# ZigBee.net
KiCad netlist of a schematic drawn in Altium Designer
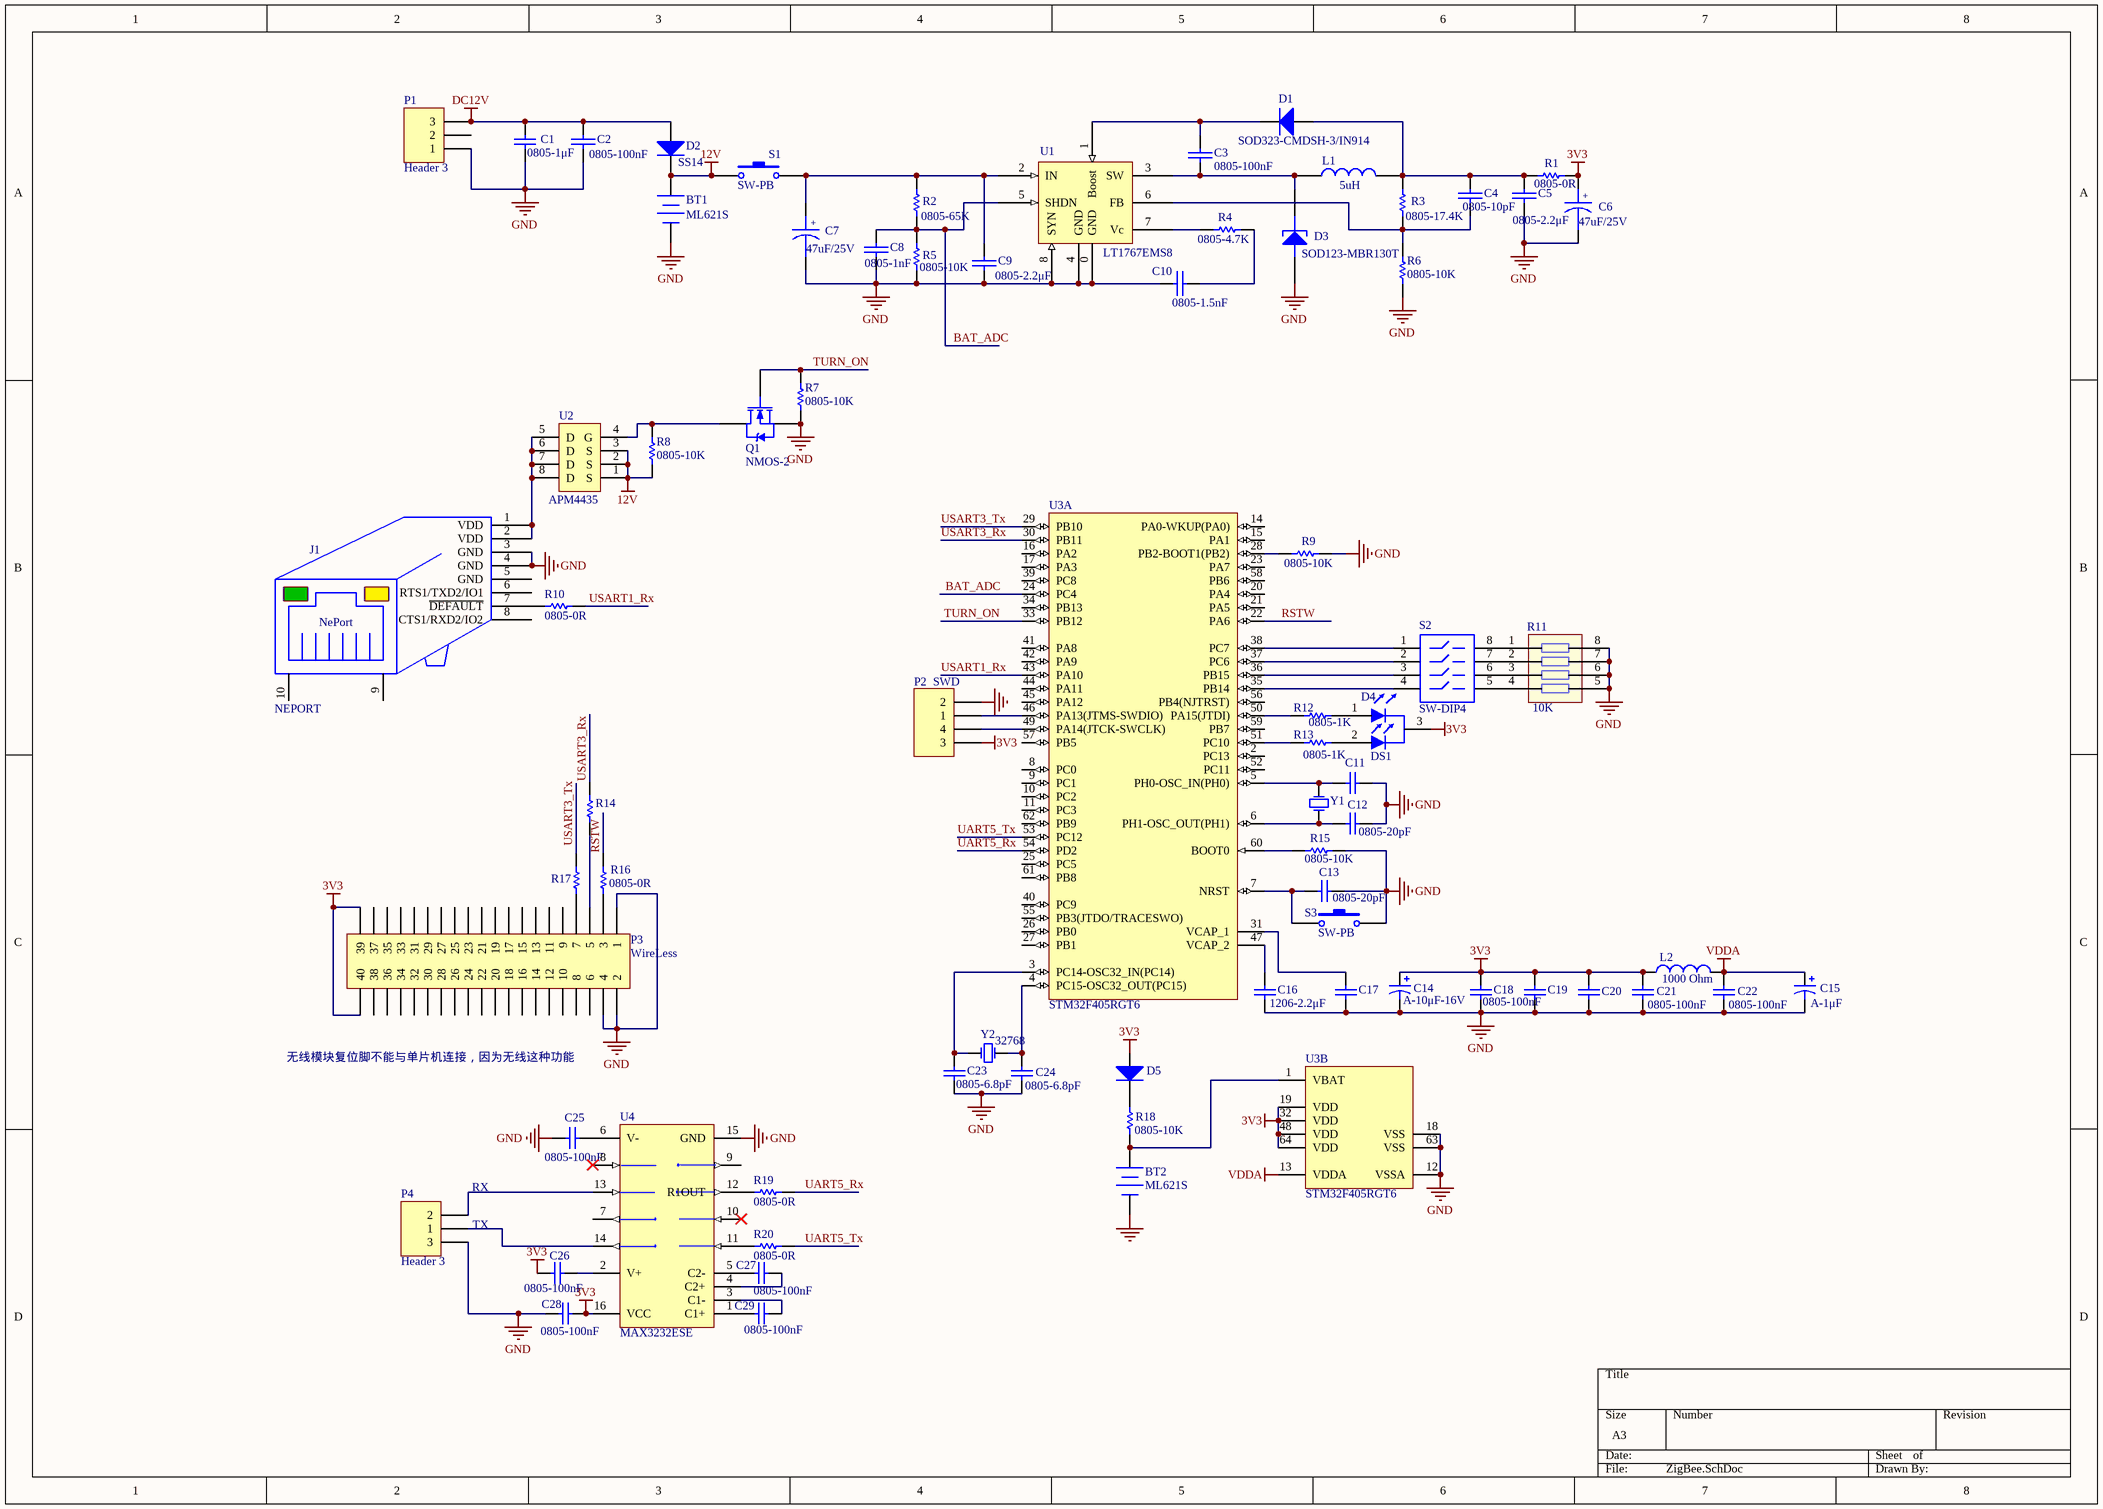
[diagram p0: ZigBee.SchDoc]

(export (version "E")
  (design (tool "Eeschema 10.0.6"))
  (components
    (comp (ref "BT1")
      (value "ML621S")
      (footprint "VH-3.96-2")
      (description "Multicell Battery")
      (fields (field (name "PUBLISHER") "Altium Limited"))
      (libsource (lib "Miscellaneous Devices") (part "Battery"))
    )
    (comp (ref "BT2")
      (value "ML621S")
      (footprint "ML621")
      (description "Multicell Battery")
      (fields (field (name "PUBLISHER") "Altium Limited"))
      (libsource (lib "Miscellaneous Devices") (part "Battery"))
    )
    (comp (ref "C1")
      (value "0805-1μF")
      (footprint "0805C")
      (description "Capacitor")
      (fields (field (name "PUBLISHER") "Altium Limited"))
      (libsource (lib "Miscellaneous Devices") (part "Cap"))
    )
    (comp (ref "C2")
      (value "0805-100nF")
      (footprint "0805C")
      (description "Capacitor")
      (libsource (lib "采集器") (part "普通电容"))
    )
    (comp (ref "C3")
      (value "0805-100nF")
      (footprint "0805C")
      (description "Capacitor")
      (libsource (lib "采集器") (part "普通电容"))
    )
    (comp (ref "C4")
      (value "0805-10pF")
      (footprint "0805C")
      (description "Capacitor")
      (libsource (lib "采集器") (part "普通电容"))
    )
    (comp (ref "C5")
      (value "0805-2.2μF")
      (footprint "0805C")
      (description "Capacitor")
      (libsource (lib "采集器") (part "普通电容"))
    )
    (comp (ref "C6")
      (value "47uF/25V")
      (footprint "SMD-47uF/25V")
      (description "Capacitor")
      (libsource (lib "采集器") (part "电解电容"))
    )
    (comp (ref "C7")
      (value "47uF/25V")
      (footprint "SMD-47uF/25V")
      (description "Capacitor")
      (libsource (lib "采集器") (part "电解电容"))
    )
    (comp (ref "C8")
      (value "0805-1nF")
      (footprint "0805C")
      (description "Capacitor")
      (libsource (lib "采集器") (part "普通电容"))
    )
    (comp (ref "C9")
      (value "0805-2.2μF")
      (footprint "0805C")
      (description "Capacitor")
      (libsource (lib "采集器") (part "普通电容"))
    )
    (comp (ref "C10")
      (value "0805-1.5nF")
      (footprint "0805C")
      (description "Capacitor")
      (libsource (lib "采集器") (part "普通电容"))
    )
    (comp (ref "C11")
      (value "0805-20pF")
      (footprint "0805C")
      (description "Capacitor")
      (fields (field (name "PUBLISHER") "Altium Limited"))
      (libsource (lib "Miscellaneous Devices") (part "Cap"))
    )
    (comp (ref "C12")
      (value "0805-20pF")
      (footprint "0805C")
      (description "Capacitor")
      (fields (field (name "PUBLISHER") "Altium Limited"))
      (libsource (lib "Miscellaneous Devices") (part "Cap"))
    )
    (comp (ref "C13")
      (value "0805-20pF")
      (footprint "0805C")
      (description "Capacitor")
      (fields (field (name "PUBLISHER") "Altium Limited"))
      (libsource (lib "Miscellaneous Devices") (part "Cap"))
    )
    (comp (ref "C14")
      (value "A-10μF-16V")
      (footprint "TANA")
      (description "Polarized Capacitor (Radial)")
      (fields (field (name "PUBLISHER") "Altium Limited"))
      (libsource (lib "Miscellaneous Devices") (part "Cap Pol1"))
    )
    (comp (ref "C15")
      (value "A-1μF")
      (footprint "TANA")
      (description "Polarized Capacitor (Radial)")
      (fields (field (name "PUBLISHER") "Altium Limited"))
      (libsource (lib "Miscellaneous Devices") (part "Cap Pol1"))
    )
    (comp (ref "C16")
      (value "1206-2.2μF")
      (description "Capacitor")
      (fields (field (name "PUBLISHER") "Altium Limited"))
      (libsource (lib "Miscellaneous Devices") (part "Cap"))
    )
    (comp (ref "C17")
      (value "1206-2.2μF")
      (description "Capacitor")
      (fields (field (name "PUBLISHER") "Altium Limited"))
      (libsource (lib "Miscellaneous Devices") (part "Cap"))
    )
    (comp (ref "C18")
      (value "0805-100nF")
      (footprint "0805C")
      (description "Capacitor")
      (fields (field (name "PUBLISHER") "Altium Limited"))
      (libsource (lib "Miscellaneous Devices") (part "Cap"))
    )
    (comp (ref "C19")
      (value "0805-100nF")
      (footprint "0805C")
      (description "Capacitor")
      (fields (field (name "PUBLISHER") "Altium Limited"))
      (libsource (lib "Miscellaneous Devices") (part "Cap"))
    )
    (comp (ref "C20")
      (value "0805-100nF")
      (footprint "0805C")
      (description "Capacitor")
      (fields (field (name "PUBLISHER") "Altium Limited"))
      (libsource (lib "Miscellaneous Devices") (part "Cap"))
    )
    (comp (ref "C21")
      (value "0805-100nF")
      (footprint "0805C")
      (description "Capacitor")
      (fields (field (name "PUBLISHER") "Altium Limited"))
      (libsource (lib "Miscellaneous Devices") (part "Cap"))
    )
    (comp (ref "C22")
      (value "0805-100nF")
      (footprint "0805C")
      (description "Capacitor")
      (fields (field (name "PUBLISHER") "Altium Limited"))
      (libsource (lib "Miscellaneous Devices") (part "Cap"))
    )
    (comp (ref "C23")
      (value "0805-6.8pF")
      (footprint "0805C")
      (description "Capacitor")
      (fields (field (name "PUBLISHER") "Altium Limited"))
      (libsource (lib "Miscellaneous Devices") (part "Cap"))
    )
    (comp (ref "C24")
      (value "0805-6.8pF")
      (footprint "0805C")
      (description "Capacitor")
      (fields (field (name "PUBLISHER") "Altium Limited"))
      (libsource (lib "Miscellaneous Devices") (part "Cap"))
    )
    (comp (ref "C25")
      (value "0805-100nF")
      (footprint "0805C")
      (description "Capacitor")
      (fields (field (name "PUBLISHER") "Altium Limited"))
      (libsource (lib "Miscellaneous Devices") (part "Cap"))
    )
    (comp (ref "C26")
      (value "0805-100nF")
      (footprint "0805C")
      (description "Capacitor")
      (fields (field (name "PUBLISHER") "Altium Limited"))
      (libsource (lib "Miscellaneous Devices") (part "Cap"))
    )
    (comp (ref "C27")
      (value "0805-100nF")
      (footprint "0805C")
      (description "Capacitor")
      (fields (field (name "PUBLISHER") "Altium Limited"))
      (libsource (lib "Miscellaneous Devices") (part "Cap"))
    )
    (comp (ref "C28")
      (value "0805-100nF")
      (footprint "0805C")
      (description "Capacitor")
      (fields (field (name "PUBLISHER") "Altium Limited"))
      (libsource (lib "Miscellaneous Devices") (part "Cap"))
    )
    (comp (ref "C29")
      (value "0805-100nF")
      (footprint "0805C")
      (description "Capacitor")
      (fields (field (name "PUBLISHER") "Altium Limited"))
      (libsource (lib "Miscellaneous Devices") (part "Cap"))
    )
    (comp (ref "D1")
      (value "SOD323-CMDSH-3/IN914")
      (footprint "SOD-323")
      (libsource (lib "采集器") (part "DIODE"))
    )
    (comp (ref "D2") (value "SS14") (footprint "DO-214AC") (libsource (lib "采集器") (part "DIODE")))
    (comp (ref "D3")
      (value "SOD123-MBR130T")
      (footprint "SOD123/X.85")
      (description "Tunnel FDiode")
      (libsource (lib "采集器") (part "TUNNEL"))
    )
    (comp (ref "D4") (value "DS1") (footprint "5MM/F5") (libsource (lib "SCHKU") (part "DS1")))
    (comp (ref "D5")
      (value "1N4148")
      (footprint "SOD-80/MLL34")
      (description "High Conductance Fast Diode")
      (fields (field (name "PUBLISHER") "Altium Limited"))
      (libsource (lib "Miscellaneous Devices") (part "Diode 1N4148"))
    )
    (comp (ref "J1")
      (value "NEPORT")
      (footprint "RJ45_8P8C")
      (description "serial to ethernet RJ45 jack")
      (libsource (lib "Neport") (part "NEPORT"))
    )
    (comp (ref "L1") (value "5uH") (footprint "SMD") (libsource (lib "采集器") (part "INDUCTOR")))
    (comp (ref "L2")
      (value "1000 Ohm")
      (footprint "INDC4516AM")
      (description "BLM41PG102SN1L\\CBW451616U900")
      (fields (field (name "PUBLISHER") "Altium Limited"))
      (libsource (lib "Miscellaneous Devices") (part "Inductor"))
    )
    (comp (ref "P1")
      (value "Header 3")
      (footprint "XH-2.54-3")
      (description "Header, 3-Pin")
      (fields (field (name "PUBLISHER") "Altium Limited"))
      (libsource (lib "Miscellaneous Connectors") (part "Header 3"))
    )
    (comp (ref "P2")
      (value "SWD")
      (footprint "HDR1X4")
      (description "Header, 4-Pin")
      (fields (field (name "PUBLISHER") "Altium Limited"))
      (libsource (lib "Miscellaneous Connectors") (part "Header 4"))
    )
    (comp (ref "P3")
      (value "WireLess")
      (footprint "SMALL/MIDDLE OEM MODEM")
      (description "Header, 20-Pin, Dual row")
      (fields (field (name "PUBLISHER") "Altium Limited"))
      (libsource (lib "Miscellaneous Connectors") (part "Header 20X2"))
    )
    (comp (ref "P4")
      (value "Header 3")
      (footprint "XH-2.54-3")
      (description "Header, 3-Pin")
      (fields (field (name "PUBLISHER") "Altium Limited"))
      (libsource (lib "") (part "Header 3_1"))
    )
    (comp (ref "Q1")
      (value "NMOS-2")
      (footprint "TO-220AB")
      (description "N-Channel Power MOSFET")
      (fields (field (name "PUBLISHER") "Altium Limited"))
      (libsource (lib "Miscellaneous Devices") (part "NMOS-2"))
    )
    (comp (ref "R1")
      (value "0805-0R")
      (footprint "0805")
      (description "Resistor")
      (fields (field (name "PUBLISHER") "Altium Limited"))
      (libsource (lib "Miscellaneous Devices") (part "Res1"))
    )
    (comp (ref "R2")
      (value "0805-65K")
      (footprint "0805")
      (description "Resistor")
      (fields (field (name "PUBLISHER") "Altium Limited"))
      (libsource (lib "Miscellaneous Devices") (part "Res1"))
    )
    (comp (ref "R3")
      (value "0805-17.4K")
      (footprint "0805")
      (description "Resistor")
      (fields (field (name "PUBLISHER") "Altium Limited"))
      (libsource (lib "Miscellaneous Devices") (part "Res1"))
    )
    (comp (ref "R4")
      (value "0805-4.7K")
      (footprint "0805")
      (description "Resistor")
      (fields (field (name "PUBLISHER") "Altium Limited"))
      (libsource (lib "Miscellaneous Devices") (part "Res1"))
    )
    (comp (ref "R5")
      (value "0805-10K")
      (footprint "0805")
      (description "Resistor")
      (fields (field (name "PUBLISHER") "Altium Limited"))
      (libsource (lib "Miscellaneous Devices") (part "Res1"))
    )
    (comp (ref "R6")
      (value "0805-10K")
      (footprint "0805")
      (description "Resistor")
      (fields (field (name "PUBLISHER") "Altium Limited"))
      (libsource (lib "Miscellaneous Devices") (part "Res1"))
    )
    (comp (ref "R7")
      (value "0805-10K")
      (footprint "0805")
      (description "Resistor")
      (fields (field (name "PUBLISHER") "Altium Limited"))
      (libsource (lib "Miscellaneous Devices") (part "Res1"))
    )
    (comp (ref "R8")
      (value "0805-10K")
      (footprint "0805")
      (description "Resistor")
      (fields (field (name "PUBLISHER") "Altium Limited"))
      (libsource (lib "Miscellaneous Devices") (part "Res1"))
    )
    (comp (ref "R9")
      (value "0805-10K")
      (footprint "0805")
      (description "Resistor")
      (fields (field (name "PUBLISHER") "Altium Limited"))
      (libsource (lib "Miscellaneous Devices") (part "Res1"))
    )
    (comp (ref "R10")
      (value "0805-0R")
      (footprint "0805")
      (description "Resistor")
      (fields (field (name "PUBLISHER") "Altium Limited"))
      (libsource (lib "Miscellaneous Devices") (part "Res1"))
    )
    (comp (ref "R11") (value "10K") (footprint "8P4R-0603") (libsource (lib "SCHKU") (part "RN4")))
    (comp (ref "R12")
      (value "0805-1K")
      (footprint "0805")
      (description "Semiconductor Resistor")
      (fields (field (name "PUBLISHER") "Altium Limited"))
      (libsource (lib "Miscellaneous Devices") (part "Res Semi"))
    )
    (comp (ref "R13")
      (value "0805-1K")
      (footprint "0805")
      (description "Semiconductor Resistor")
      (fields (field (name "PUBLISHER") "Altium Limited"))
      (libsource (lib "Miscellaneous Devices") (part "Res Semi"))
    )
    (comp (ref "R14")
      (value "0805-0R")
      (footprint "0805")
      (description "Resistor")
      (fields (field (name "PUBLISHER") "Altium Limited"))
      (libsource (lib "Miscellaneous Devices") (part "Res1"))
    )
    (comp (ref "R15")
      (value "0805-10K")
      (footprint "0805")
      (description "Resistor")
      (fields (field (name "PUBLISHER") "Altium Limited"))
      (libsource (lib "Miscellaneous Devices") (part "Res1"))
    )
    (comp (ref "R16")
      (value "0805-0R")
      (footprint "0805")
      (description "Resistor")
      (fields (field (name "PUBLISHER") "Altium Limited"))
      (libsource (lib "Miscellaneous Devices") (part "Res1"))
    )
    (comp (ref "R17")
      (value "0805-0R")
      (footprint "0805")
      (description "Resistor")
      (fields (field (name "PUBLISHER") "Altium Limited"))
      (libsource (lib "Miscellaneous Devices") (part "Res1"))
    )
    (comp (ref "R18")
      (value "0805-10K")
      (footprint "0805")
      (description "Resistor")
      (fields (field (name "PUBLISHER") "Altium Limited"))
      (libsource (lib "Miscellaneous Devices") (part "Res1"))
    )
    (comp (ref "R19")
      (value "0805-0R")
      (footprint "0805")
      (description "Resistor")
      (fields (field (name "PUBLISHER") "Altium Limited"))
      (libsource (lib "Miscellaneous Devices") (part "Res1"))
    )
    (comp (ref "R20")
      (value "0805-0R")
      (footprint "0805")
      (description "Resistor")
      (fields (field (name "PUBLISHER") "Altium Limited"))
      (libsource (lib "Miscellaneous Devices") (part "Res1"))
    )
    (comp (ref "S1")
      (value "SW-PB")
      (footprint "XH-2.54-2")
      (description "Switch")
      (fields (field (name "PUBLISHER") "Altium Limited"))
      (libsource (lib "Miscellaneous Devices") (part "SW-PB"))
    )
    (comp (ref "S2")
      (value "SW-DIP4")
      (footprint "DIP-8")
      (description "DIP Switch")
      (fields (field (name "PUBLISHER") "Altium Limited"))
      (libsource (lib "Miscellaneous Devices") (part "SW-DIP4"))
    )
    (comp (ref "S3")
      (value "SW-PB")
      (footprint "SW3*4*2MM")
      (description "Switch")
      (fields (field (name "PUBLISHER") "Altium Limited"))
      (libsource (lib "") (part "SW-PB_1"))
    )
    (comp (ref "U1") (value "LT1767EMS8") (footprint "MS8_N") (libsource (lib "采集器") (part "LT1767EMS8")))
    (comp (ref "U2") (value "APM4435") (footprint "SOP-8M") (libsource (lib "BLACKBOX") (part "APM4435")))
    (comp (ref "U3")
      (value "STM32F405RGT6")
      (footprint "TQFP64_M")
      (fields (field (name "MANUFACTURER") "STMicroelectronics"))
      (libsource (lib "STMicroelectronics STM32 F4") (part "STM32F405RGT6"))
    )
    (comp (ref "U4")
      (value "MAX3232ESE")
      (footprint "NSO16_N")
      (description "3.0V TO 5.5V, Low-Power, up to 1Mbps, True RS-232 Transceiver Using Four 0.1µF External Capacitor")
      (fields (field (name "PUBLISHER") "Altium Limited"))
      (libsource (lib "Maxim Communication Transceiver") (part "MAX3232ESE"))
    )
    (comp (ref "Y1")
      (value "8MHz")
      (footprint "XTAL")
      (description "Crystal Oscillator")
      (fields (field (name "PUBLISHER") "Altium Limited"))
      (libsource (lib "Miscellaneous Devices") (part "XTAL"))
    )
    (comp (ref "Y2")
      (value "32768")
      (footprint "1206CY")
      (description "Crystal Oscillator")
      (fields (field (name "PUBLISHER") "Altium Limited"))
      (libsource (lib "Miscellaneous Devices") (part "XTAL"))
    )
  )
  (nets
    (net (code "1") (name "/BAT_ADC") (class "Default")
      (node (ref "C8") (pin "1") (pinfunction "1_1") (pintype "passive"))
      (node (ref "R2") (pin "1") (pinfunction "1_1") (pintype "passive"))
      (node (ref "R5") (pin "2") (pinfunction "2_2") (pintype "passive"))
      (node (ref "U1") (pin "5") (pinfunction "SHDN_5") (pintype "input"))
      (node (ref "U3") (pin "24") (pinfunction "PC4_24") (pintype "bidirectional"))
    )
    (net (code "2") (name "/RSTW") (class "Default")
      (node (ref "R16") (pin "1") (pinfunction "1_1") (pintype "passive"))
      (node (ref "U3") (pin "22") (pinfunction "PA6_22") (pintype "bidirectional"))
    )
    (net (code "3") (name "/TURN_ON") (class "Default")
      (node (ref "Q1") (pin "1") (pinfunction "G_1") (pintype "passive"))
      (node (ref "R7") (pin "2") (pinfunction "2_2") (pintype "passive"))
      (node (ref "U3") (pin "33") (pinfunction "PB12_33") (pintype "bidirectional"))
    )
    (net (code "4") (name "/UART5_Rx") (class "Default")
      (node (ref "R19") (pin "2") (pinfunction "2_2") (pintype "passive"))
      (node (ref "U3") (pin "54") (pinfunction "PD2_54") (pintype "bidirectional"))
    )
    (net (code "5") (name "/UART5_Tx") (class "Default")
      (node (ref "R20") (pin "2") (pinfunction "2_2") (pintype "passive"))
      (node (ref "U3") (pin "53") (pinfunction "PC12_53") (pintype "bidirectional"))
    )
    (net (code "6") (name "/USART1_Rx") (class "Default")
      (node (ref "R10") (pin "1") (pinfunction "1_1") (pintype "passive"))
      (node (ref "U3") (pin "43") (pinfunction "PA10_43") (pintype "bidirectional"))
    )
    (net (code "7") (name "/USART3_Rx") (class "Default")
      (node (ref "R14") (pin "1") (pinfunction "1_1") (pintype "passive"))
      (node (ref "U3") (pin "30") (pinfunction "PB11_30") (pintype "bidirectional"))
    )
    (net (code "8") (name "/USART3_Tx") (class "Default")
      (node (ref "R17") (pin "1") (pinfunction "1_1") (pintype "passive"))
      (node (ref "U3") (pin "29") (pinfunction "PB10_29") (pintype "bidirectional"))
    )
    (net (code "9") (name "3V3") (class "Default")
      (node (ref "C14") (pin "1") (pinfunction "1_1") (pintype "passive"))
      (node (ref "C18") (pin "2") (pinfunction "2_2") (pintype "passive"))
      (node (ref "C19") (pin "2") (pinfunction "2_2") (pintype "passive"))
      (node (ref "C20") (pin "2") (pinfunction "2_2") (pintype "passive"))
      (node (ref "C21") (pin "2") (pinfunction "2_2") (pintype "passive"))
      (node (ref "C26") (pin "2") (pinfunction "2_2") (pintype "passive"))
      (node (ref "C28") (pin "1") (pinfunction "1_1") (pintype "passive"))
      (node (ref "C6") (pin "1") (pinfunction "1_1") (pintype "passive"))
      (node (ref "D4") (pin "3") (pinfunction "3_3") (pintype "passive"))
      (node (ref "D5") (pin "1") (pinfunction "A_1") (pintype "passive"))
      (node (ref "L2") (pin "1") (pinfunction "1_1") (pintype "passive"))
      (node (ref "P2") (pin "3") (pinfunction "3_3") (pintype "passive"))
      (node (ref "P3") (pin "39") (pinfunction "39_39") (pintype "passive"))
      (node (ref "P3") (pin "40") (pinfunction "40_40") (pintype "passive"))
      (node (ref "R1") (pin "2") (pinfunction "2_2") (pintype "passive"))
      (node (ref "U3") (pin "19") (pinfunction "VDD_19") (pintype "power_in"))
      (node (ref "U3") (pin "32") (pinfunction "VDD_32") (pintype "power_in"))
      (node (ref "U3") (pin "48") (pinfunction "VDD_48") (pintype "power_in"))
      (node (ref "U3") (pin "64") (pinfunction "VDD_64") (pintype "power_in"))
      (node (ref "U4") (pin "16") (pinfunction "VCC_16") (pintype "power_in"))
    )
    (net (code "10") (name "12V") (class "Default")
      (node (ref "BT1") (pin "2") (pinfunction "+_2") (pintype "passive"))
      (node (ref "D2") (pin "2") (pinfunction "K_2") (pintype "passive"))
      (node (ref "R8") (pin "1") (pinfunction "1_1") (pintype "passive"))
      (node (ref "S1") (pin "2") (pinfunction "2_2") (pintype "passive"))
      (node (ref "U2") (pin "1") (pinfunction "S_1") (pintype "passive"))
      (node (ref "U2") (pin "2") (pinfunction "S_2") (pintype "passive"))
      (node (ref "U2") (pin "3") (pinfunction "S_3") (pintype "passive"))
    )
    (net (code "11") (name "DC12V") (class "Default")
      (node (ref "C1") (pin "1") (pinfunction "1_1") (pintype "passive"))
      (node (ref "C2") (pin "1") (pinfunction "1_1") (pintype "passive"))
      (node (ref "D2") (pin "1") (pinfunction "A_1") (pintype "passive"))
      (node (ref "P1") (pin "3") (pinfunction "3_3") (pintype "passive"))
    )
    (net (code "12") (name "GND") (class "Default")
      (node (ref "BT1") (pin "1") (pinfunction "-_1") (pintype "passive"))
      (node (ref "BT2") (pin "1") (pinfunction "-_1") (pintype "passive"))
      (node (ref "C1") (pin "2") (pinfunction "2_2") (pintype "passive"))
      (node (ref "C10") (pin "1") (pinfunction "1_1") (pintype "passive"))
      (node (ref "C11") (pin "1") (pinfunction "1_1") (pintype "passive"))
      (node (ref "C12") (pin "1") (pinfunction "1_1") (pintype "passive"))
      (node (ref "C13") (pin "1") (pinfunction "1_1") (pintype "passive"))
      (node (ref "C14") (pin "2") (pinfunction "2_2") (pintype "passive"))
      (node (ref "C15") (pin "2") (pinfunction "2_2") (pintype "passive"))
      (node (ref "C16") (pin "1") (pinfunction "1_1") (pintype "passive"))
      (node (ref "C17") (pin "1") (pinfunction "1_1") (pintype "passive"))
      (node (ref "C18") (pin "1") (pinfunction "1_1") (pintype "passive"))
      (node (ref "C19") (pin "1") (pinfunction "1_1") (pintype "passive"))
      (node (ref "C2") (pin "2") (pinfunction "2_2") (pintype "passive"))
      (node (ref "C20") (pin "1") (pinfunction "1_1") (pintype "passive"))
      (node (ref "C21") (pin "1") (pinfunction "1_1") (pintype "passive"))
      (node (ref "C22") (pin "1") (pinfunction "1_1") (pintype "passive"))
      (node (ref "C23") (pin "2") (pinfunction "2_2") (pintype "passive"))
      (node (ref "C24") (pin "2") (pinfunction "2_2") (pintype "passive"))
      (node (ref "C25") (pin "2") (pinfunction "2_2") (pintype "passive"))
      (node (ref "C28") (pin "2") (pinfunction "2_2") (pintype "passive"))
      (node (ref "C5") (pin "2") (pinfunction "2_2") (pintype "passive"))
      (node (ref "C6") (pin "2") (pinfunction "2_2") (pintype "passive"))
      (node (ref "C7") (pin "2") (pinfunction "2_2") (pintype "passive"))
      (node (ref "C8") (pin "2") (pinfunction "2_2") (pintype "passive"))
      (node (ref "C9") (pin "2") (pinfunction "2_2") (pintype "passive"))
      (node (ref "D3") (pin "1") (pinfunction "A_1") (pintype "passive"))
      (node (ref "J1") (pin "3") (pinfunction "GND_3") (pintype "passive"))
      (node (ref "J1") (pin "4") (pinfunction "GND_4") (pintype "passive"))
      (node (ref "P1") (pin "1") (pinfunction "1_1") (pintype "passive"))
      (node (ref "P2") (pin "2") (pinfunction "2_2") (pintype "passive"))
      (node (ref "P3") (pin "1") (pinfunction "1_1") (pintype "passive"))
      (node (ref "P3") (pin "2") (pinfunction "2_2") (pintype "passive"))
      (node (ref "P3") (pin "4") (pinfunction "4_4") (pintype "passive"))
      (node (ref "P4") (pin "3") (pinfunction "3_3") (pintype "passive"))
      (node (ref "Q1") (pin "3") (pinfunction "D_3") (pintype "passive"))
      (node (ref "R11") (pin "5") (pinfunction "5_5") (pintype "passive"))
      (node (ref "R11") (pin "6") (pinfunction "6_6") (pintype "passive"))
      (node (ref "R11") (pin "7") (pinfunction "7_7") (pintype "passive"))
      (node (ref "R11") (pin "8") (pinfunction "8_8") (pintype "passive"))
      (node (ref "R15") (pin "2") (pinfunction "2_2") (pintype "passive"))
      (node (ref "R5") (pin "1") (pinfunction "1_1") (pintype "passive"))
      (node (ref "R6") (pin "1") (pinfunction "1_1") (pintype "passive"))
      (node (ref "R7") (pin "1") (pinfunction "1_1") (pintype "passive"))
      (node (ref "R9") (pin "2") (pinfunction "2_2") (pintype "passive"))
      (node (ref "S3") (pin "2") (pinfunction "2_2") (pintype "passive"))
      (node (ref "U1") (pin "0") (pinfunction "GND_0") (pintype "passive"))
      (node (ref "U1") (pin "4") (pinfunction "GND_4") (pintype "passive"))
      (node (ref "U1") (pin "8") (pinfunction "SYN_8") (pintype "input"))
      (node (ref "U3") (pin "12") (pinfunction "VSSA_12") (pintype "power_in"))
      (node (ref "U3") (pin "18") (pinfunction "VSS_18") (pintype "power_in"))
      (node (ref "U3") (pin "63") (pinfunction "VSS_63") (pintype "power_in"))
      (node (ref "U4") (pin "15") (pinfunction "GND_15") (pintype "power_in"))
    )
    (net (code "13") (name "Net-(BT2-+)") (class "Default")
      (node (ref "BT2") (pin "2") (pinfunction "+_2") (pintype "passive"))
      (node (ref "R18") (pin "2") (pinfunction "2_2") (pintype "passive"))
      (node (ref "U3") (pin "1") (pinfunction "VBAT_1") (pintype "power_in"))
    )
    (net (code "14") (name "Net-(C10-Pad2)") (class "Default")
      (node (ref "C10") (pin "2") (pinfunction "2_2") (pintype "passive"))
      (node (ref "R4") (pin "1") (pinfunction "1_1") (pintype "passive"))
    )
    (net (code "15") (name "Net-(D1-A)") (class "Default")
      (node (ref "C4") (pin "1") (pinfunction "1_1") (pintype "passive"))
      (node (ref "C5") (pin "1") (pinfunction "1_1") (pintype "passive"))
      (node (ref "D1") (pin "1") (pinfunction "A_1") (pintype "passive"))
      (node (ref "L1") (pin "2") (pinfunction "2_2") (pintype "passive"))
      (node (ref "R1") (pin "1") (pinfunction "1_1") (pintype "passive"))
      (node (ref "R3") (pin "2") (pinfunction "2_2") (pintype "passive"))
    )
    (net (code "16") (name "Net-(D1-K)") (class "Default")
      (node (ref "C3") (pin "1") (pinfunction "1_1") (pintype "passive"))
      (node (ref "D1") (pin "2") (pinfunction "K_2") (pintype "passive"))
      (node (ref "U1") (pin "1") (pinfunction "Boost_1") (pintype "input"))
    )
    (net (code "17") (name "Net-(D3-K)") (class "Default")
      (node (ref "C3") (pin "2") (pinfunction "2_2") (pintype "passive"))
      (node (ref "D3") (pin "2") (pinfunction "K_2") (pintype "passive"))
      (node (ref "L1") (pin "1") (pinfunction "1_1") (pintype "passive"))
      (node (ref "U1") (pin "3") (pinfunction "SW_3") (pintype "passive"))
    )
    (net (code "18") (name "Net-(D4-Pad1)") (class "Default")
      (node (ref "D4") (pin "1") (pinfunction "1_1") (pintype "passive"))
      (node (ref "R12") (pin "2") (pinfunction "2_2") (pintype "passive"))
    )
    (net (code "19") (name "Net-(D4-Pad2)") (class "Default")
      (node (ref "D4") (pin "2") (pinfunction "2_2") (pintype "passive"))
      (node (ref "R13") (pin "2") (pinfunction "2_2") (pintype "passive"))
    )
    (net (code "20") (name "Net-(D5-K)") (class "Default")
      (node (ref "D5") (pin "2") (pinfunction "K_2") (pintype "passive"))
      (node (ref "R18") (pin "1") (pinfunction "1_1") (pintype "passive"))
    )
    (net (code "21") (name "Net-(J1-VDD-Pad1)") (class "Default")
      (node (ref "J1") (pin "1") (pinfunction "VDD_1") (pintype "passive"))
      (node (ref "J1") (pin "2") (pinfunction "VDD_2") (pintype "passive"))
      (node (ref "U2") (pin "5") (pinfunction "D_5") (pintype "passive"))
      (node (ref "U2") (pin "6") (pinfunction "D_6") (pintype "passive"))
      (node (ref "U2") (pin "7") (pinfunction "D_7") (pintype "passive"))
      (node (ref "U2") (pin "8") (pinfunction "D_8") (pintype "passive"))
    )
    (net (code "22") (name "Net-(J1-~{DEFAULT})") (class "Default")
      (node (ref "J1") (pin "7") (pinfunction "~{DEFAULT}_7") (pintype "passive"))
      (node (ref "R10") (pin "2") (pinfunction "2_2") (pintype "passive"))
    )
    (net (code "23") (name "Net-(P3-Pad3)") (class "Default")
      (node (ref "P3") (pin "3") (pinfunction "3_3") (pintype "passive"))
      (node (ref "R16") (pin "2") (pinfunction "2_2") (pintype "passive"))
    )
    (net (code "24") (name "Net-(P3-Pad5)") (class "Default")
      (node (ref "P3") (pin "5") (pinfunction "5_5") (pintype "passive"))
      (node (ref "R14") (pin "2") (pinfunction "2_2") (pintype "passive"))
    )
    (net (code "25") (name "Net-(P3-Pad7)") (class "Default")
      (node (ref "P3") (pin "7") (pinfunction "7_7") (pintype "passive"))
      (node (ref "R17") (pin "2") (pinfunction "2_2") (pintype "passive"))
    )
    (net (code "26") (name "Net-(Q1-S)") (class "Default")
      (node (ref "Q1") (pin "2") (pinfunction "S_2") (pintype "passive"))
      (node (ref "R8") (pin "2") (pinfunction "2_2") (pintype "passive"))
      (node (ref "U2") (pin "4") (pinfunction "G_4") (pintype "passive"))
    )
    (net (code "27") (name "Net-(R11-Pad1)") (class "Default")
      (node (ref "R11") (pin "1") (pinfunction "1_1") (pintype "passive"))
      (node (ref "S2") (pin "8") (pinfunction "8_8") (pintype "passive"))
    )
    (net (code "28") (name "Net-(R11-Pad2)") (class "Default")
      (node (ref "R11") (pin "2") (pinfunction "2_2") (pintype "passive"))
      (node (ref "S2") (pin "7") (pinfunction "7_7") (pintype "passive"))
    )
    (net (code "29") (name "Net-(R11-Pad3)") (class "Default")
      (node (ref "R11") (pin "3") (pinfunction "3_3") (pintype "passive"))
      (node (ref "S2") (pin "6") (pinfunction "6_6") (pintype "passive"))
    )
    (net (code "30") (name "Net-(R11-Pad4)") (class "Default")
      (node (ref "R11") (pin "4") (pinfunction "4_4") (pintype "passive"))
      (node (ref "S2") (pin "5") (pinfunction "5_5") (pintype "passive"))
    )
    (net (code "31") (name "Net-(U1-FB)") (class "Default")
      (node (ref "C4") (pin "2") (pinfunction "2_2") (pintype "passive"))
      (node (ref "R3") (pin "1") (pinfunction "1_1") (pintype "passive"))
      (node (ref "R6") (pin "2") (pinfunction "2_2") (pintype "passive"))
      (node (ref "U1") (pin "6") (pinfunction "FB_6") (pintype "passive"))
    )
    (net (code "32") (name "Net-(U1-IN)") (class "Default")
      (node (ref "C7") (pin "1") (pinfunction "1_1") (pintype "passive"))
      (node (ref "C9") (pin "1") (pinfunction "1_1") (pintype "passive"))
      (node (ref "R2") (pin "2") (pinfunction "2_2") (pintype "passive"))
      (node (ref "S1") (pin "1") (pinfunction "1_1") (pintype "passive"))
      (node (ref "U1") (pin "2") (pinfunction "IN_2") (pintype "input"))
    )
    (net (code "33") (name "Net-(U1-Vc)") (class "Default")
      (node (ref "R4") (pin "2") (pinfunction "2_2") (pintype "passive"))
      (node (ref "U1") (pin "7") (pinfunction "Vc_7") (pintype "passive"))
    )
    (net (code "34") (name "Net-(U3A-BOOT0)") (class "Default")
      (node (ref "R15") (pin "1") (pinfunction "1_1") (pintype "passive"))
      (node (ref "U3") (pin "60") (pinfunction "BOOT0_60") (pintype "input"))
    )
    (net (code "35") (name "Net-(U3A-NRST)") (class "Default")
      (node (ref "C13") (pin "2") (pinfunction "2_2") (pintype "passive"))
      (node (ref "S3") (pin "1") (pinfunction "1_1") (pintype "passive"))
      (node (ref "U3") (pin "7") (pinfunction "NRST_7") (pintype "bidirectional"))
    )
    (net (code "36") (name "Net-(U3A-PA13(JTMS-SWDIO))") (class "Default")
      (node (ref "P2") (pin "1") (pinfunction "1_1") (pintype "passive"))
      (node (ref "U3") (pin "46") (pinfunction "PA13(JTMS-SWDIO)_46") (pintype "bidirectional"))
    )
    (net (code "37") (name "Net-(U3A-PA14(JTCK-SWCLK))") (class "Default")
      (node (ref "P2") (pin "4") (pinfunction "4_4") (pintype "passive"))
      (node (ref "U3") (pin "49") (pinfunction "PA14(JTCK-SWCLK)_49") (pintype "bidirectional"))
    )
    (net (code "38") (name "Net-(U3A-PA15(JTDI))") (class "Default")
      (node (ref "R12") (pin "1") (pinfunction "1_1") (pintype "passive"))
      (node (ref "U3") (pin "50") (pinfunction "PA15(JTDI)_50") (pintype "bidirectional"))
    )
    (net (code "39") (name "Net-(U3A-PB2-BOOT1(PB2))") (class "Default")
      (node (ref "R9") (pin "1") (pinfunction "1_1") (pintype "passive"))
      (node (ref "U3") (pin "28") (pinfunction "PB2-BOOT1(PB2)_28") (pintype "bidirectional"))
    )
    (net (code "40") (name "Net-(U3A-PB14)") (class "Default")
      (node (ref "S2") (pin "4") (pinfunction "4_4") (pintype "passive"))
      (node (ref "U3") (pin "35") (pinfunction "PB14_35") (pintype "bidirectional"))
    )
    (net (code "41") (name "Net-(U3A-PB15)") (class "Default")
      (node (ref "S2") (pin "3") (pinfunction "3_3") (pintype "passive"))
      (node (ref "U3") (pin "36") (pinfunction "PB15_36") (pintype "bidirectional"))
    )
    (net (code "42") (name "Net-(U3A-PC6)") (class "Default")
      (node (ref "S2") (pin "2") (pinfunction "2_2") (pintype "passive"))
      (node (ref "U3") (pin "37") (pinfunction "PC6_37") (pintype "bidirectional"))
    )
    (net (code "43") (name "Net-(U3A-PC7)") (class "Default")
      (node (ref "S2") (pin "1") (pinfunction "1_1") (pintype "passive"))
      (node (ref "U3") (pin "38") (pinfunction "PC7_38") (pintype "bidirectional"))
    )
    (net (code "44") (name "Net-(U3A-PC10)") (class "Default")
      (node (ref "R13") (pin "1") (pinfunction "1_1") (pintype "passive"))
      (node (ref "U3") (pin "51") (pinfunction "PC10_51") (pintype "bidirectional"))
    )
    (net (code "45") (name "Net-(U3A-PC14-OSC32_IN(PC14))") (class "Default")
      (node (ref "C23") (pin "1") (pinfunction "1_1") (pintype "passive"))
      (node (ref "U3") (pin "3") (pinfunction "PC14-OSC32_IN(PC14)_3") (pintype "bidirectional"))
      (node (ref "Y2") (pin "2") (pinfunction "OSC2_2") (pintype "passive"))
    )
    (net (code "46") (name "Net-(U3A-PC15-OSC32_OUT(PC15))") (class "Default")
      (node (ref "C24") (pin "1") (pinfunction "1_1") (pintype "passive"))
      (node (ref "U3") (pin "4") (pinfunction "PC15-OSC32_OUT(PC15)_4") (pintype "bidirectional"))
      (node (ref "Y2") (pin "1") (pinfunction "OSC1_1") (pintype "passive"))
    )
    (net (code "47") (name "Net-(U3A-PH0-OSC_IN(PH0))") (class "Default")
      (node (ref "C11") (pin "2") (pinfunction "2_2") (pintype "passive"))
      (node (ref "U3") (pin "5") (pinfunction "PH0-OSC_IN(PH0)_5") (pintype "bidirectional"))
      (node (ref "Y1") (pin "2") (pinfunction "OSC2_2") (pintype "passive"))
    )
    (net (code "48") (name "Net-(U3A-PH1-OSC_OUT(PH1))") (class "Default")
      (node (ref "C12") (pin "2") (pinfunction "2_2") (pintype "passive"))
      (node (ref "U3") (pin "6") (pinfunction "PH1-OSC_OUT(PH1)_6") (pintype "bidirectional"))
      (node (ref "Y1") (pin "1") (pinfunction "OSC1_1") (pintype "passive"))
    )
    (net (code "49") (name "Net-(U3A-VCAP_1)") (class "Default")
      (node (ref "C17") (pin "2") (pinfunction "2_2") (pintype "passive"))
      (node (ref "U3") (pin "31") (pinfunction "VCAP_1_31") (pintype "power_in"))
    )
    (net (code "50") (name "Net-(U3A-VCAP_2)") (class "Default")
      (node (ref "C16") (pin "2") (pinfunction "2_2") (pintype "passive"))
      (node (ref "U3") (pin "47") (pinfunction "VCAP_2_47") (pintype "power_in"))
    )
    (net (code "51") (name "Net-(U4-C1+)") (class "Default")
      (node (ref "C29") (pin "2") (pinfunction "2_2") (pintype "passive"))
      (node (ref "U4") (pin "1") (pinfunction "C1+_1") (pintype "passive"))
    )
    (net (code "52") (name "Net-(U4-C1-)") (class "Default")
      (node (ref "C29") (pin "1") (pinfunction "1_1") (pintype "passive"))
      (node (ref "U4") (pin "3") (pinfunction "C1-_3") (pintype "passive"))
    )
    (net (code "53") (name "Net-(U4-C2+)") (class "Default")
      (node (ref "C27") (pin "1") (pinfunction "1_1") (pintype "passive"))
      (node (ref "U4") (pin "4") (pinfunction "C2+_4") (pintype "passive"))
    )
    (net (code "54") (name "Net-(U4-C2-)") (class "Default")
      (node (ref "C27") (pin "2") (pinfunction "2_2") (pintype "passive"))
      (node (ref "U4") (pin "5") (pinfunction "C2-_5") (pintype "passive"))
    )
    (net (code "55") (name "Net-(U4-R1IN)") (class "Default")
      (node (ref "P4") (pin "2") (pinfunction "2_2") (pintype "passive"))
      (node (ref "U4") (pin "13") (pinfunction "R1IN_13") (pintype "input"))
    )
    (net (code "56") (name "Net-(U4-R1OUT)") (class "Default")
      (node (ref "R19") (pin "1") (pinfunction "1_1") (pintype "passive"))
      (node (ref "U4") (pin "12") (pinfunction "R1OUT_12") (pintype "output"))
    )
    (net (code "57") (name "Net-(U4-T1IN)") (class "Default")
      (node (ref "R20") (pin "1") (pinfunction "1_1") (pintype "passive"))
      (node (ref "U4") (pin "11") (pinfunction "T1IN_11") (pintype "input"))
    )
    (net (code "58") (name "Net-(U4-T1OUT)") (class "Default")
      (node (ref "P4") (pin "1") (pinfunction "1_1") (pintype "passive"))
      (node (ref "U4") (pin "14") (pinfunction "T1OUT_14") (pintype "output"))
    )
    (net (code "59") (name "Net-(U4-V+)") (class "Default")
      (node (ref "C26") (pin "1") (pinfunction "1_1") (pintype "passive"))
      (node (ref "U4") (pin "2") (pinfunction "V+_2") (pintype "power_in"))
    )
    (net (code "60") (name "Net-(U4-V-)") (class "Default")
      (node (ref "C25") (pin "1") (pinfunction "1_1") (pintype "passive"))
      (node (ref "U4") (pin "6") (pinfunction "V-_6") (pintype "power_in"))
    )
    (net (code "61") (name "VDDA") (class "Default")
      (node (ref "C15") (pin "1") (pinfunction "1_1") (pintype "passive"))
      (node (ref "C22") (pin "2") (pinfunction "2_2") (pintype "passive"))
      (node (ref "L2") (pin "2") (pinfunction "2_2") (pintype "passive"))
      (node (ref "U3") (pin "13") (pinfunction "VDDA_13") (pintype "power_in"))
    )
    (net (code "62") (name "unconnected-(J1-CTS1{slash}RXD2{slash}IO2-Pad8)") (class "Default")
      (node (ref "J1") (pin "8") (pinfunction "CTS1/RXD2/IO2_8") (pintype "passive"))
    )
    (net (code "63") (name "unconnected-(J1-GND-Pad5)") (class "Default")
      (node (ref "J1") (pin "5") (pinfunction "GND_5") (pintype "passive"))
    )
    (net (code "64") (name "unconnected-(J1-RTS1{slash}TXD2{slash}IO1-Pad6)") (class "Default")
      (node (ref "J1") (pin "6") (pinfunction "RTS1/TXD2/IO1_6") (pintype "passive"))
    )
    (net (code "65") (name "unconnected-(J1-SHELL-Pad9)") (class "Default")
      (node (ref "J1") (pin "9") (pinfunction "SHELL_9") (pintype "passive"))
    )
    (net (code "66") (name "unconnected-(J1-SHELL-Pad10)") (class "Default")
      (node (ref "J1") (pin "10") (pinfunction "SHELL_10") (pintype "passive"))
    )
    (net (code "67") (name "unconnected-(P1-Pad2)") (class "Default")
      (node (ref "P1") (pin "2") (pinfunction "2_2") (pintype "passive"))
    )
    (net (code "68") (name "unconnected-(P3-Pad6)") (class "Default")
      (node (ref "P3") (pin "6") (pinfunction "6_6") (pintype "passive"))
    )
    (net (code "69") (name "unconnected-(P3-Pad8)") (class "Default")
      (node (ref "P3") (pin "8") (pinfunction "8_8") (pintype "passive"))
    )
    (net (code "70") (name "unconnected-(P3-Pad9)") (class "Default")
      (node (ref "P3") (pin "9") (pinfunction "9_9") (pintype "passive"))
    )
    (net (code "71") (name "unconnected-(P3-Pad10)") (class "Default")
      (node (ref "P3") (pin "10") (pinfunction "10_10") (pintype "passive"))
    )
    (net (code "72") (name "unconnected-(P3-Pad11)") (class "Default")
      (node (ref "P3") (pin "11") (pinfunction "11_11") (pintype "passive"))
    )
    (net (code "73") (name "unconnected-(P3-Pad12)") (class "Default")
      (node (ref "P3") (pin "12") (pinfunction "12_12") (pintype "passive"))
    )
    (net (code "74") (name "unconnected-(P3-Pad13)") (class "Default")
      (node (ref "P3") (pin "13") (pinfunction "13_13") (pintype "passive"))
    )
    (net (code "75") (name "unconnected-(P3-Pad14)") (class "Default")
      (node (ref "P3") (pin "14") (pinfunction "14_14") (pintype "passive"))
    )
    (net (code "76") (name "unconnected-(P3-Pad15)") (class "Default")
      (node (ref "P3") (pin "15") (pinfunction "15_15") (pintype "passive"))
    )
    (net (code "77") (name "unconnected-(P3-Pad16)") (class "Default")
      (node (ref "P3") (pin "16") (pinfunction "16_16") (pintype "passive"))
    )
    (net (code "78") (name "unconnected-(P3-Pad17)") (class "Default")
      (node (ref "P3") (pin "17") (pinfunction "17_17") (pintype "passive"))
    )
    (net (code "79") (name "unconnected-(P3-Pad18)") (class "Default")
      (node (ref "P3") (pin "18") (pinfunction "18_18") (pintype "passive"))
    )
    (net (code "80") (name "unconnected-(P3-Pad19)") (class "Default")
      (node (ref "P3") (pin "19") (pinfunction "19_19") (pintype "passive"))
    )
    (net (code "81") (name "unconnected-(P3-Pad20)") (class "Default")
      (node (ref "P3") (pin "20") (pinfunction "20_20") (pintype "passive"))
    )
    (net (code "82") (name "unconnected-(P3-Pad21)") (class "Default")
      (node (ref "P3") (pin "21") (pinfunction "21_21") (pintype "passive"))
    )
    (net (code "83") (name "unconnected-(P3-Pad22)") (class "Default")
      (node (ref "P3") (pin "22") (pinfunction "22_22") (pintype "passive"))
    )
    (net (code "84") (name "unconnected-(P3-Pad23)") (class "Default")
      (node (ref "P3") (pin "23") (pinfunction "23_23") (pintype "passive"))
    )
    (net (code "85") (name "unconnected-(P3-Pad24)") (class "Default")
      (node (ref "P3") (pin "24") (pinfunction "24_24") (pintype "passive"))
    )
    (net (code "86") (name "unconnected-(P3-Pad25)") (class "Default")
      (node (ref "P3") (pin "25") (pinfunction "25_25") (pintype "passive"))
    )
    (net (code "87") (name "unconnected-(P3-Pad26)") (class "Default")
      (node (ref "P3") (pin "26") (pinfunction "26_26") (pintype "passive"))
    )
    (net (code "88") (name "unconnected-(P3-Pad27)") (class "Default")
      (node (ref "P3") (pin "27") (pinfunction "27_27") (pintype "passive"))
    )
    (net (code "89") (name "unconnected-(P3-Pad28)") (class "Default")
      (node (ref "P3") (pin "28") (pinfunction "28_28") (pintype "passive"))
    )
    (net (code "90") (name "unconnected-(P3-Pad29)") (class "Default")
      (node (ref "P3") (pin "29") (pinfunction "29_29") (pintype "passive"))
    )
    (net (code "91") (name "unconnected-(P3-Pad30)") (class "Default")
      (node (ref "P3") (pin "30") (pinfunction "30_30") (pintype "passive"))
    )
    (net (code "92") (name "unconnected-(P3-Pad31)") (class "Default")
      (node (ref "P3") (pin "31") (pinfunction "31_31") (pintype "passive"))
    )
    (net (code "93") (name "unconnected-(P3-Pad32)") (class "Default")
      (node (ref "P3") (pin "32") (pinfunction "32_32") (pintype "passive"))
    )
    (net (code "94") (name "unconnected-(P3-Pad33)") (class "Default")
      (node (ref "P3") (pin "33") (pinfunction "33_33") (pintype "passive"))
    )
    (net (code "95") (name "unconnected-(P3-Pad34)") (class "Default")
      (node (ref "P3") (pin "34") (pinfunction "34_34") (pintype "passive"))
    )
    (net (code "96") (name "unconnected-(P3-Pad35)") (class "Default")
      (node (ref "P3") (pin "35") (pinfunction "35_35") (pintype "passive"))
    )
    (net (code "97") (name "unconnected-(P3-Pad36)") (class "Default")
      (node (ref "P3") (pin "36") (pinfunction "36_36") (pintype "passive"))
    )
    (net (code "98") (name "unconnected-(P3-Pad37)") (class "Default")
      (node (ref "P3") (pin "37") (pinfunction "37_37") (pintype "passive"))
    )
    (net (code "99") (name "unconnected-(P3-Pad38)") (class "Default")
      (node (ref "P3") (pin "38") (pinfunction "38_38") (pintype "passive"))
    )
    (net (code "100") (name "unconnected-(U3A-PA0-WKUP(PA0)-Pad14)") (class "Default")
      (node (ref "U3") (pin "14") (pinfunction "PA0-WKUP(PA0)_14") (pintype "bidirectional"))
    )
    (net (code "101") (name "unconnected-(U3A-PA1-Pad15)") (class "Default")
      (node (ref "U3") (pin "15") (pinfunction "PA1_15") (pintype "bidirectional"))
    )
    (net (code "102") (name "unconnected-(U3A-PA2-Pad16)") (class "Default")
      (node (ref "U3") (pin "16") (pinfunction "PA2_16") (pintype "bidirectional"))
    )
    (net (code "103") (name "unconnected-(U3A-PA3-Pad17)") (class "Default")
      (node (ref "U3") (pin "17") (pinfunction "PA3_17") (pintype "bidirectional"))
    )
    (net (code "104") (name "unconnected-(U3A-PA4-Pad20)") (class "Default")
      (node (ref "U3") (pin "20") (pinfunction "PA4_20") (pintype "bidirectional"))
    )
    (net (code "105") (name "unconnected-(U3A-PA5-Pad21)") (class "Default")
      (node (ref "U3") (pin "21") (pinfunction "PA5_21") (pintype "bidirectional"))
    )
    (net (code "106") (name "unconnected-(U3A-PA7-Pad23)") (class "Default")
      (node (ref "U3") (pin "23") (pinfunction "PA7_23") (pintype "bidirectional"))
    )
    (net (code "107") (name "unconnected-(U3A-PA8-Pad41)") (class "Default")
      (node (ref "U3") (pin "41") (pinfunction "PA8_41") (pintype "bidirectional"))
    )
    (net (code "108") (name "unconnected-(U3A-PA9-Pad42)") (class "Default")
      (node (ref "U3") (pin "42") (pinfunction "PA9_42") (pintype "bidirectional"))
    )
    (net (code "109") (name "unconnected-(U3A-PA11-Pad44)") (class "Default")
      (node (ref "U3") (pin "44") (pinfunction "PA11_44") (pintype "bidirectional"))
    )
    (net (code "110") (name "unconnected-(U3A-PA12-Pad45)") (class "Default")
      (node (ref "U3") (pin "45") (pinfunction "PA12_45") (pintype "bidirectional"))
    )
    (net (code "111") (name "unconnected-(U3A-PB0-Pad26)") (class "Default")
      (node (ref "U3") (pin "26") (pinfunction "PB0_26") (pintype "bidirectional"))
    )
    (net (code "112") (name "unconnected-(U3A-PB1-Pad27)") (class "Default")
      (node (ref "U3") (pin "27") (pinfunction "PB1_27") (pintype "bidirectional"))
    )
    (net (code "113") (name "unconnected-(U3A-PB3(JTDO{slash}TRACESWO)-Pad55)") (class "Default")
      (node (ref "U3") (pin "55") (pinfunction "PB3(JTDO/TRACESWO)_55") (pintype "bidirectional"))
    )
    (net (code "114") (name "unconnected-(U3A-PB4(NJTRST)-Pad56)") (class "Default")
      (node (ref "U3") (pin "56") (pinfunction "PB4(NJTRST)_56") (pintype "bidirectional"))
    )
    (net (code "115") (name "unconnected-(U3A-PB5-Pad57)") (class "Default")
      (node (ref "U3") (pin "57") (pinfunction "PB5_57") (pintype "bidirectional"))
    )
    (net (code "116") (name "unconnected-(U3A-PB6-Pad58)") (class "Default")
      (node (ref "U3") (pin "58") (pinfunction "PB6_58") (pintype "bidirectional"))
    )
    (net (code "117") (name "unconnected-(U3A-PB7-Pad59)") (class "Default")
      (node (ref "U3") (pin "59") (pinfunction "PB7_59") (pintype "bidirectional"))
    )
    (net (code "118") (name "unconnected-(U3A-PB8-Pad61)") (class "Default")
      (node (ref "U3") (pin "61") (pinfunction "PB8_61") (pintype "bidirectional"))
    )
    (net (code "119") (name "unconnected-(U3A-PB9-Pad62)") (class "Default")
      (node (ref "U3") (pin "62") (pinfunction "PB9_62") (pintype "bidirectional"))
    )
    (net (code "120") (name "unconnected-(U3A-PB13-Pad34)") (class "Default")
      (node (ref "U3") (pin "34") (pinfunction "PB13_34") (pintype "bidirectional"))
    )
    (net (code "121") (name "unconnected-(U3A-PC0-Pad8)") (class "Default")
      (node (ref "U3") (pin "8") (pinfunction "PC0_8") (pintype "bidirectional"))
    )
    (net (code "122") (name "unconnected-(U3A-PC1-Pad9)") (class "Default")
      (node (ref "U3") (pin "9") (pinfunction "PC1_9") (pintype "bidirectional"))
    )
    (net (code "123") (name "unconnected-(U3A-PC2-Pad10)") (class "Default")
      (node (ref "U3") (pin "10") (pinfunction "PC2_10") (pintype "bidirectional"))
    )
    (net (code "124") (name "unconnected-(U3A-PC3-Pad11)") (class "Default")
      (node (ref "U3") (pin "11") (pinfunction "PC3_11") (pintype "bidirectional"))
    )
    (net (code "125") (name "unconnected-(U3A-PC5-Pad25)") (class "Default")
      (node (ref "U3") (pin "25") (pinfunction "PC5_25") (pintype "bidirectional"))
    )
    (net (code "126") (name "unconnected-(U3A-PC8-Pad39)") (class "Default")
      (node (ref "U3") (pin "39") (pinfunction "PC8_39") (pintype "bidirectional"))
    )
    (net (code "127") (name "unconnected-(U3A-PC9-Pad40)") (class "Default")
      (node (ref "U3") (pin "40") (pinfunction "PC9_40") (pintype "bidirectional"))
    )
    (net (code "128") (name "unconnected-(U3A-PC11-Pad52)") (class "Default")
      (node (ref "U3") (pin "52") (pinfunction "PC11_52") (pintype "bidirectional"))
    )
    (net (code "129") (name "unconnected-(U3A-PC13-Pad2)") (class "Default")
      (node (ref "U3") (pin "2") (pinfunction "PC13_2") (pintype "bidirectional"))
    )
    (net (code "130") (name "unconnected-(U4-R2IN-Pad8)") (class "Default")
      (node (ref "U4") (pin "8") (pinfunction "R2IN_8") (pintype "input+no_connect"))
    )
    (net (code "131") (name "unconnected-(U4-R2OUT-Pad9)") (class "Default")
      (node (ref "U4") (pin "9") (pinfunction "R2OUT_9") (pintype "output"))
    )
    (net (code "132") (name "unconnected-(U4-T2IN-Pad10)") (class "Default")
      (node (ref "U4") (pin "10") (pinfunction "T2IN_10") (pintype "input+no_connect"))
    )
    (net (code "133") (name "unconnected-(U4-T2OUT-Pad7)") (class "Default")
      (node (ref "U4") (pin "7") (pinfunction "T2OUT_7") (pintype "output"))
    )
  )
)
